# Ghidorah5.net
KiCad netlist of a schematic drawn in EAGLE
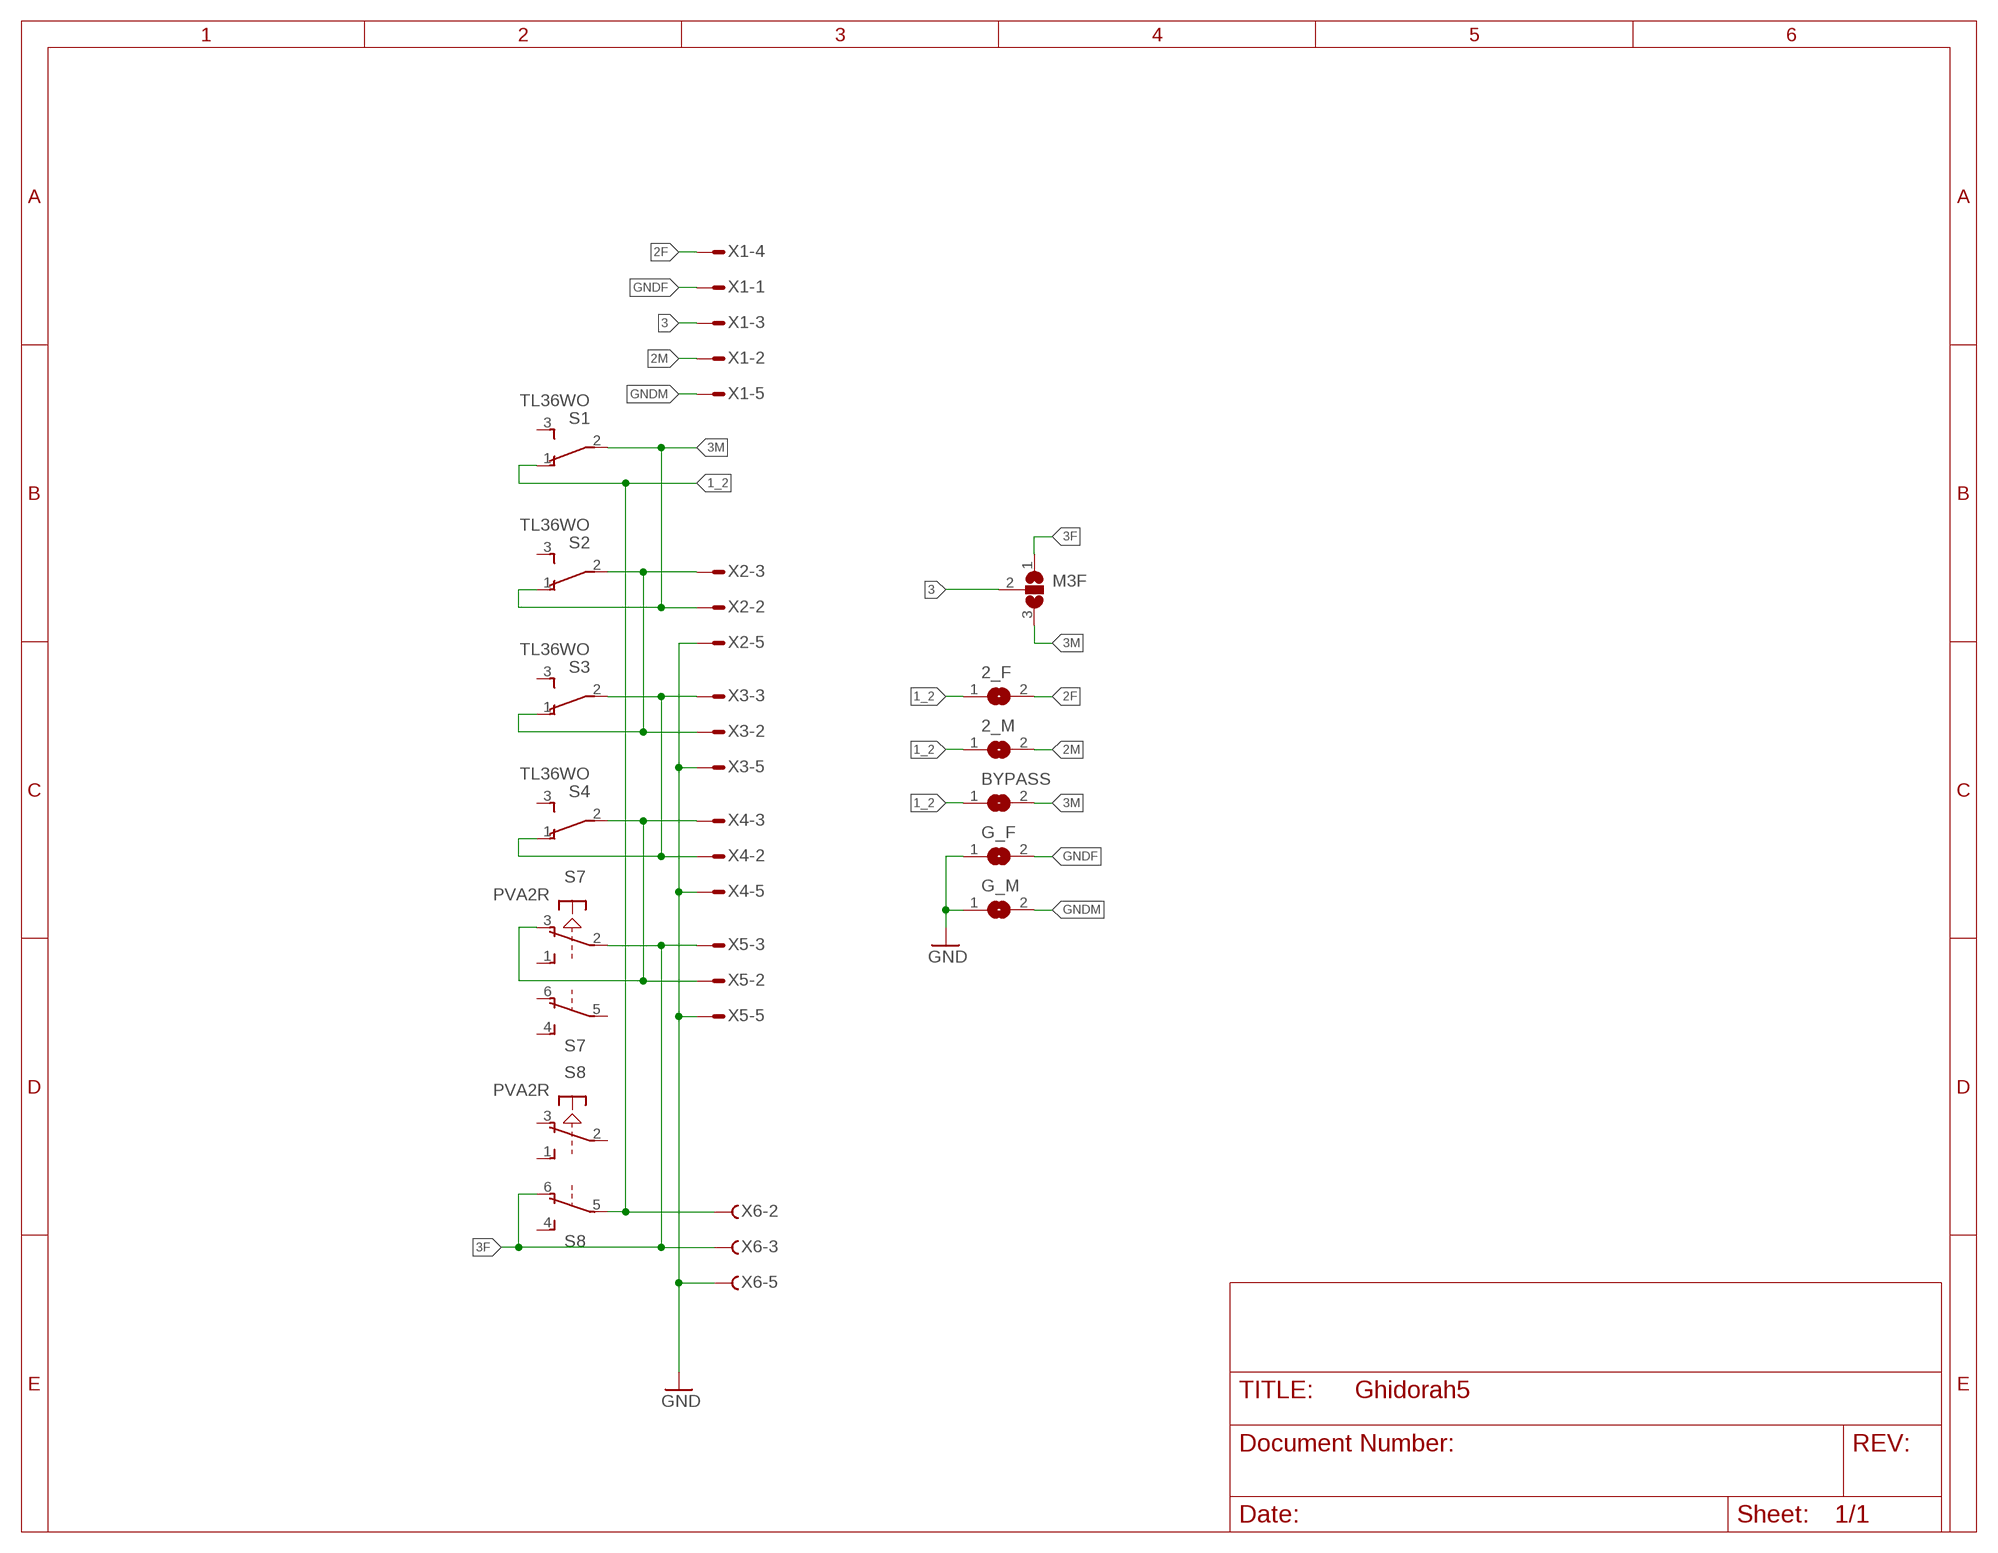
[diagram p0: schematic, sheet 1]

(export (version "E")
  (design (tool "Eeschema 10.0.6"))
  (components
    (comp (ref "2_F") (value "SJ") (footprint "eagle-import:SJ") (libsource (lib "eagle-import") (part "SJ")))
    (comp (ref "2_M") (value "SJ") (footprint "eagle-import:SJ") (libsource (lib "eagle-import") (part "SJ")))
    (comp (ref "BYPASS")
      (value "SJ")
      (footprint "eagle-import:SJ")
      (libsource (lib "eagle-import") (part "SJ"))
    )
    (comp (ref "G_F") (value "SJ") (footprint "eagle-import:SJ") (libsource (lib "eagle-import") (part "SJ")))
    (comp (ref "G_M") (value "SJ") (footprint "eagle-import:SJ") (libsource (lib "eagle-import") (part "SJ")))
    (comp (ref "M3F")
      (value "SJ2W")
      (footprint "eagle-import:SJ_2")
      (libsource (lib "eagle-import") (part "SJ2W"))
    )
    (comp (ref "S1")
      (value "TL36WO")
      (footprint "eagle-import:TL3XWO")
      (libsource (lib "eagle-import") (part "TL36WO"))
    )
    (comp (ref "S2")
      (value "TL36WO")
      (footprint "eagle-import:TL3XWO")
      (libsource (lib "eagle-import") (part "TL36WO"))
    )
    (comp (ref "S3")
      (value "TL36WO")
      (footprint "eagle-import:TL3XWO")
      (libsource (lib "eagle-import") (part "TL36WO"))
    )
    (comp (ref "S4")
      (value "TL36WO")
      (footprint "eagle-import:TL3XWO")
      (libsource (lib "eagle-import") (part "TL36WO"))
    )
    (comp (ref "S7")
      (value "PVA2R")
      (footprint "eagle-import:PVA2R")
      (libsource (lib "eagle-import") (part "PVA2R"))
    )
    (comp (ref "S8")
      (value "PVA2R")
      (footprint "eagle-import:PVA2R")
      (libsource (lib "eagle-import") (part "PVA2R"))
    )
    (comp (ref "X1")
      (value "M09DS")
      (footprint "eagle-import:M09D")
      (libsource (lib "eagle-import") (part "M09?SD"))
    )
    (comp (ref "X2")
      (value "M09DS")
      (footprint "eagle-import:M09D")
      (libsource (lib "eagle-import") (part "M09?SD"))
    )
    (comp (ref "X3")
      (value "M09DS")
      (footprint "eagle-import:M09D")
      (libsource (lib "eagle-import") (part "M09?SD"))
    )
    (comp (ref "X4")
      (value "M09DS")
      (footprint "eagle-import:M09D")
      (libsource (lib "eagle-import") (part "M09?SD"))
    )
    (comp (ref "X5")
      (value "M09VS")
      (footprint "eagle-import:M09V")
      (libsource (lib "eagle-import") (part "M09?SV"))
    )
    (comp (ref "X6")
      (value "F09VS")
      (footprint "eagle-import:F09V")
      (libsource (lib "eagle-import") (part "F09?SV"))
    )
  )
  (nets
    (net (code "1") (name "1_2") (class "Default")
      (node (ref "2_F") (pin "1") (pinfunction "1_1") (pintype "passive"))
      (node (ref "2_M") (pin "1") (pinfunction "1_1") (pintype "passive"))
      (node (ref "BYPASS") (pin "1") (pinfunction "1_1") (pintype "passive"))
      (node (ref "S1") (pin "1") (pinfunction "O_1") (pintype "passive"))
      (node (ref "S8") (pin "5") (pinfunction "P_5") (pintype "passive"))
      (node (ref "X6") (pin "2") (pinfunction "F_2") (pintype "passive"))
    )
    (net (code "2") (name "2F") (class "Default")
      (node (ref "2_F") (pin "2") (pinfunction "2_2") (pintype "passive"))
      (node (ref "X1") (pin "4") (pinfunction "M_4") (pintype "passive"))
    )
    (net (code "3") (name "2M") (class "Default")
      (node (ref "2_M") (pin "2") (pinfunction "2_2") (pintype "passive"))
      (node (ref "X1") (pin "2") (pinfunction "M_2") (pintype "passive"))
    )
    (net (code "4") (name "3") (class "Default")
      (node (ref "M3F") (pin "2") (pinfunction "2_2") (pintype "passive"))
      (node (ref "X1") (pin "3") (pinfunction "M_3") (pintype "passive"))
    )
    (net (code "5") (name "3F") (class "Default")
      (node (ref "M3F") (pin "1") (pinfunction "1_1") (pintype "passive"))
      (node (ref "S7") (pin "2") (pinfunction "P_2") (pintype "passive"))
      (node (ref "S8") (pin "6") (pinfunction "O_6") (pintype "passive"))
      (node (ref "X5") (pin "3") (pinfunction "M_3") (pintype "passive"))
      (node (ref "X6") (pin "3") (pinfunction "F_3") (pintype "passive"))
    )
    (net (code "6") (name "3M") (class "Default")
      (node (ref "BYPASS") (pin "2") (pinfunction "2_2") (pintype "passive"))
      (node (ref "M3F") (pin "3") (pinfunction "3_3") (pintype "passive"))
      (node (ref "S1") (pin "2") (pinfunction "P_2") (pintype "passive"))
      (node (ref "S2") (pin "1") (pinfunction "O_1") (pintype "passive"))
      (node (ref "X2") (pin "2") (pinfunction "M_2") (pintype "passive"))
    )
    (net (code "7") (name "GND") (class "Default")
      (node (ref "G_F") (pin "1") (pinfunction "1_1") (pintype "passive"))
      (node (ref "G_M") (pin "1") (pinfunction "1_1") (pintype "passive"))
      (node (ref "X2") (pin "5") (pinfunction "M_5") (pintype "passive"))
      (node (ref "X3") (pin "5") (pinfunction "M_5") (pintype "passive"))
      (node (ref "X4") (pin "5") (pinfunction "M_5") (pintype "passive"))
      (node (ref "X5") (pin "5") (pinfunction "M_5") (pintype "passive"))
      (node (ref "X6") (pin "5") (pinfunction "F_5") (pintype "passive"))
    )
    (net (code "8") (name "GNDF") (class "Default")
      (node (ref "G_F") (pin "2") (pinfunction "2_2") (pintype "passive"))
      (node (ref "X1") (pin "1") (pinfunction "M_1") (pintype "passive"))
    )
    (net (code "9") (name "GNDM") (class "Default")
      (node (ref "G_M") (pin "2") (pinfunction "2_2") (pintype "passive"))
      (node (ref "X1") (pin "5") (pinfunction "M_5") (pintype "passive"))
    )
    (net (code "10") (name "Net-(S2-P)") (class "Default")
      (node (ref "S2") (pin "2") (pinfunction "P_2") (pintype "passive"))
      (node (ref "S3") (pin "1") (pinfunction "O_1") (pintype "passive"))
      (node (ref "X2") (pin "3") (pinfunction "M_3") (pintype "passive"))
      (node (ref "X3") (pin "2") (pinfunction "M_2") (pintype "passive"))
    )
    (net (code "11") (name "Net-(S3-P)") (class "Default")
      (node (ref "S3") (pin "2") (pinfunction "P_2") (pintype "passive"))
      (node (ref "S4") (pin "1") (pinfunction "O_1") (pintype "passive"))
      (node (ref "X3") (pin "3") (pinfunction "M_3") (pintype "passive"))
      (node (ref "X4") (pin "2") (pinfunction "M_2") (pintype "passive"))
    )
    (net (code "12") (name "Net-(S4-P)") (class "Default")
      (node (ref "S4") (pin "2") (pinfunction "P_2") (pintype "passive"))
      (node (ref "S7") (pin "3") (pinfunction "O_3") (pintype "passive"))
      (node (ref "X4") (pin "3") (pinfunction "M_3") (pintype "passive"))
      (node (ref "X5") (pin "2") (pinfunction "M_2") (pintype "passive"))
    )
    (net (code "13") (name "unconnected-(S1-S-Pad3)") (class "Default")
      (node (ref "S1") (pin "3") (pinfunction "S_3") (pintype "passive"))
    )
    (net (code "14") (name "unconnected-(S2-S-Pad3)") (class "Default")
      (node (ref "S2") (pin "3") (pinfunction "S_3") (pintype "passive"))
    )
    (net (code "15") (name "unconnected-(S3-S-Pad3)") (class "Default")
      (node (ref "S3") (pin "3") (pinfunction "S_3") (pintype "passive"))
    )
    (net (code "16") (name "unconnected-(S4-S-Pad3)") (class "Default")
      (node (ref "S4") (pin "3") (pinfunction "S_3") (pintype "passive"))
    )
    (net (code "17") (name "unconnected-(S7A-S-Pad1)") (class "Default")
      (node (ref "S7") (pin "1") (pinfunction "S_1") (pintype "passive"))
    )
    (net (code "18") (name "unconnected-(S7B-O-Pad6)") (class "Default")
      (node (ref "S7") (pin "6") (pinfunction "O_6") (pintype "passive"))
    )
    (net (code "19") (name "unconnected-(S7B-P-Pad5)") (class "Default")
      (node (ref "S7") (pin "5") (pinfunction "P_5") (pintype "passive"))
    )
    (net (code "20") (name "unconnected-(S7B-S-Pad4)") (class "Default")
      (node (ref "S7") (pin "4") (pinfunction "S_4") (pintype "passive"))
    )
    (net (code "21") (name "unconnected-(S8A-O-Pad3)") (class "Default")
      (node (ref "S8") (pin "3") (pinfunction "O_3") (pintype "passive"))
    )
    (net (code "22") (name "unconnected-(S8A-P-Pad2)") (class "Default")
      (node (ref "S8") (pin "2") (pinfunction "P_2") (pintype "passive"))
    )
    (net (code "23") (name "unconnected-(S8A-S-Pad1)") (class "Default")
      (node (ref "S8") (pin "1") (pinfunction "S_1") (pintype "passive"))
    )
    (net (code "24") (name "unconnected-(S8B-S-Pad4)") (class "Default")
      (node (ref "S8") (pin "4") (pinfunction "S_4") (pintype "passive"))
    )
  )
)
